# first_model.net
KiCad netlist of a schematic drawn in EAGLE
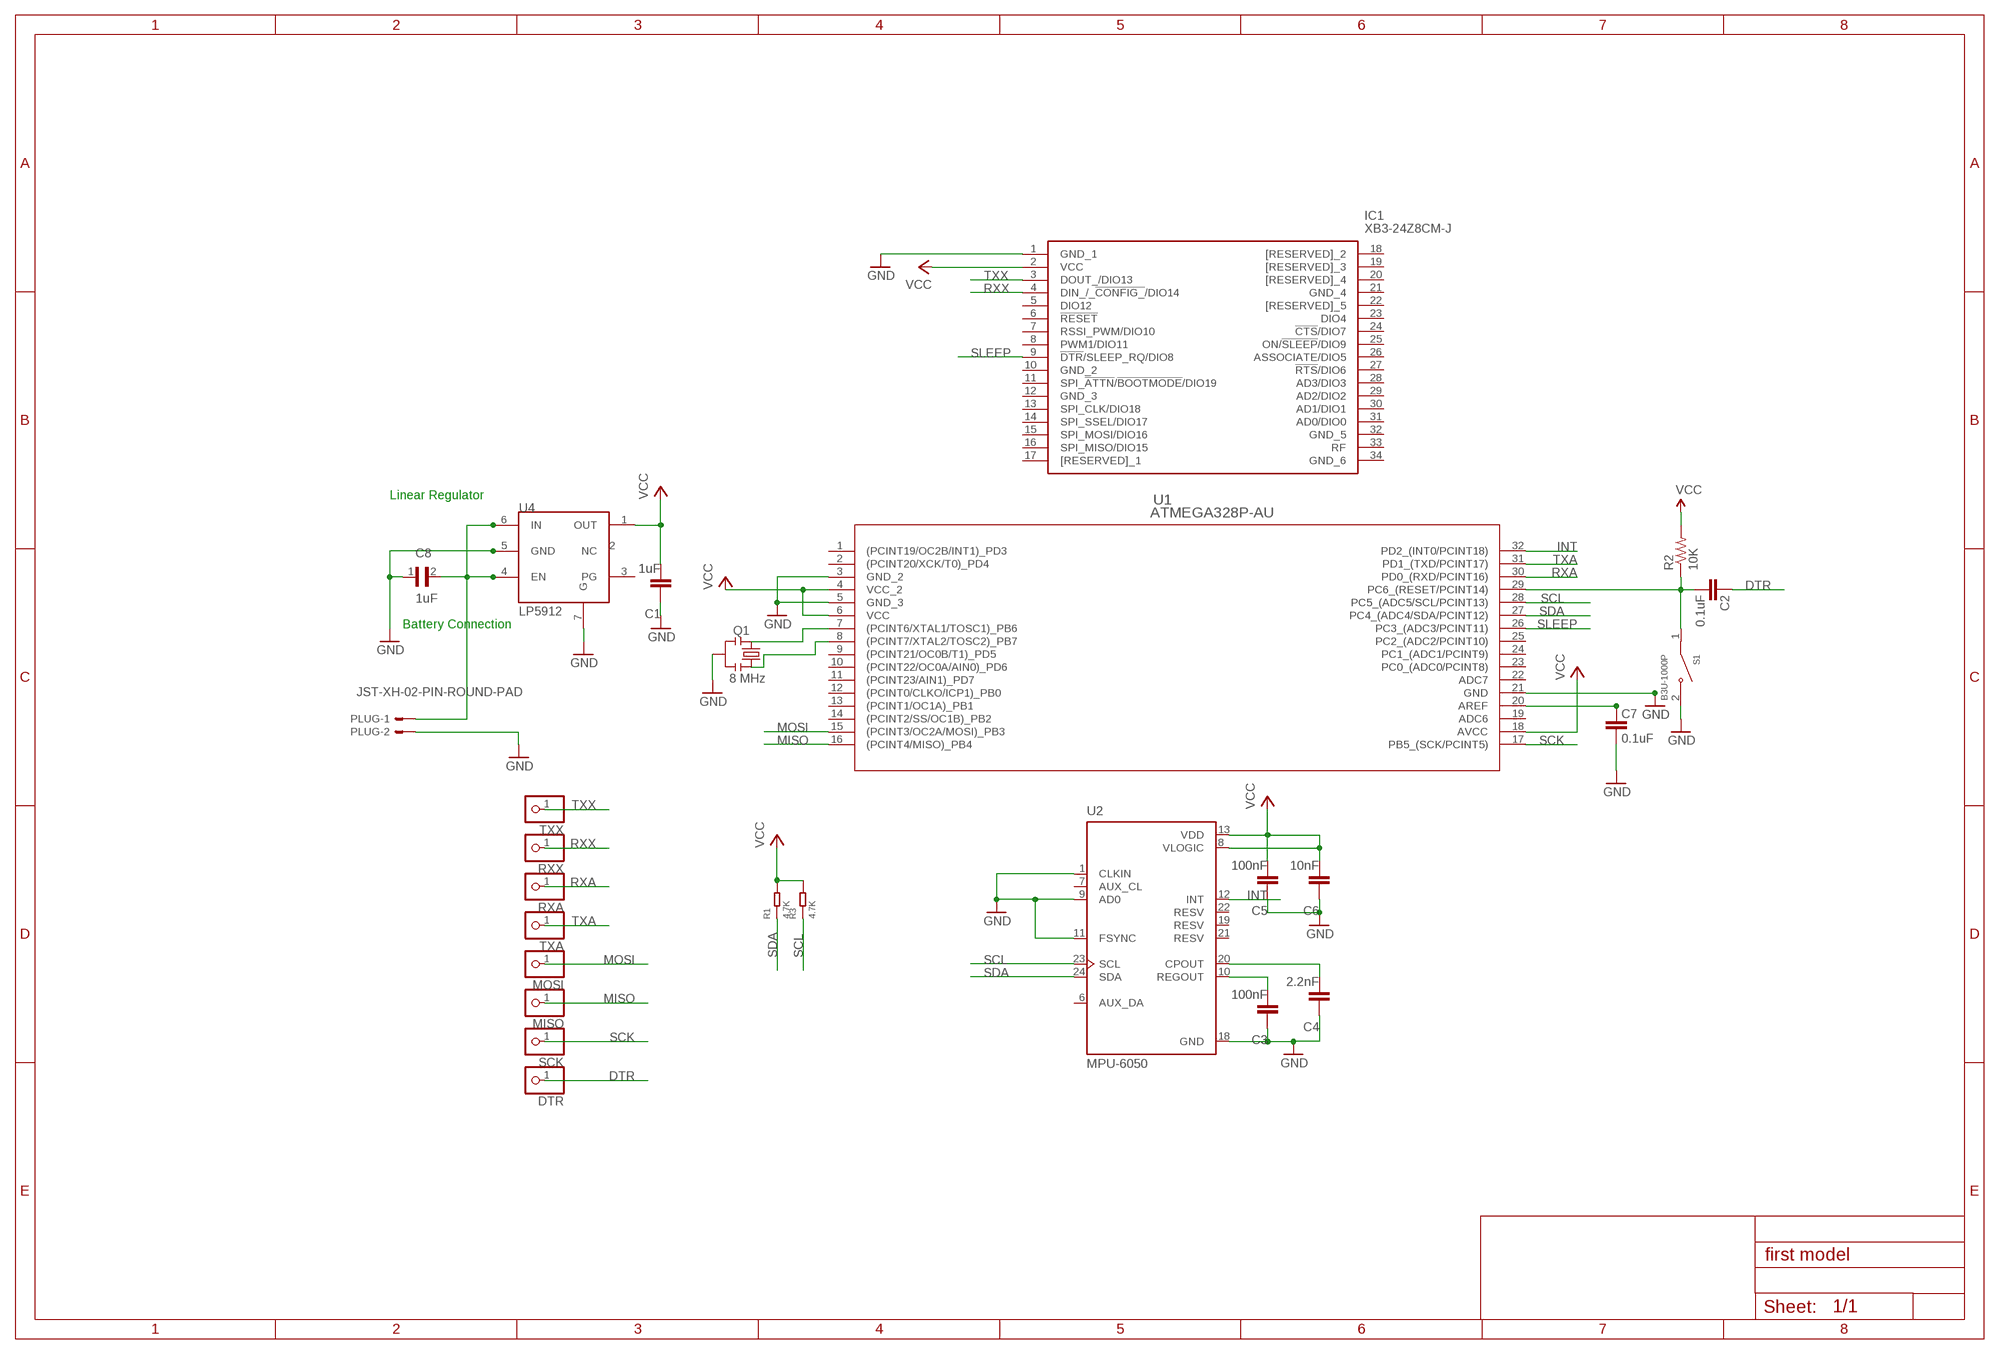
[diagram p0: schematic, sheet 1]

(export (version "E")
  (design (tool "Eeschema 10.0.6"))
  (components
    (comp (ref "C1")
      (value "1uF")
      (footprint "eagle-import:C0603")
      (libsource (lib "eagle-import") (part "C-EUC0603"))
    )
    (comp (ref "C2")
      (value "0.1uF")
      (footprint "eagle-import:0603-CAP")
      (libsource (lib "eagle-import") (part "CAP0603-CAP"))
    )
    (comp (ref "C3")
      (value "100nF")
      (footprint "eagle-import:C0603")
      (libsource (lib "eagle-import") (part "C-EUC0603"))
    )
    (comp (ref "C4")
      (value "2.2nF")
      (footprint "eagle-import:C0603")
      (libsource (lib "eagle-import") (part "C-EUC0603"))
    )
    (comp (ref "C5")
      (value "100nF")
      (footprint "eagle-import:C0603")
      (libsource (lib "eagle-import") (part "C-EUC0603"))
    )
    (comp (ref "C6")
      (value "10nF")
      (footprint "eagle-import:C0603")
      (libsource (lib "eagle-import") (part "C-EUC0603"))
    )
    (comp (ref "C7")
      (value "0.1uF")
      (footprint "eagle-import:0603-CAP")
      (libsource (lib "eagle-import") (part "CAP0603-CAP"))
    )
    (comp (ref "C8")
      (value "1uF")
      (footprint "eagle-import:CAPC1005X71N")
      (fields (field (name "MF") "AVX") (field (name "MP") "0402YD105MAT2A"))
      (libsource (lib "eagle-import") (part "0402YD105MAT2A"))
    )
    (comp (ref "DTR")
      (value "DTR")
      (footprint "eagle-import:1X01")
      (libsource (lib "eagle-import") (part "PINHD-1X1"))
    )
    (comp (ref "IC1")
      (value "XB3-24Z8CM-J")
      (footprint "eagle-import:XB324Z8CMJ")
      (fields (field (name "MOUSER_PART_NUMBER") "888-XB3-24Z8CM-J"))
      (libsource (lib "eagle-import") (part "XB3-24Z8CM-J"))
    )
    (comp (ref "MISO")
      (value "PINHD-1X1")
      (footprint "eagle-import:1X01")
      (libsource (lib "eagle-import") (part "PINHD-1X1"))
    )
    (comp (ref "MOSI")
      (value "PINHD-1X1")
      (footprint "eagle-import:1X01")
      (libsource (lib "eagle-import") (part "PINHD-1X1"))
    )
    (comp (ref "PLUG")
      (value "JST-XH-02-PIN-ROUND-PAD")
      (footprint "eagle-import:JST-XH-02-PACKAGE-ROUND-PAD")
      (libsource (lib "eagle-import") (part "JST-XH-02-PIN-ROUND-PAD"))
    )
    (comp (ref "Q1")
      (value "8 MHz")
      (footprint "eagle-import:RESONATOR-SMD-1_1")
      (libsource (lib "eagle-import") (part "RESONATOR1{colon}1"))
    )
    (comp (ref "R1")
      (value "4.7K")
      (footprint "eagle-import:R0402")
      (fields (field (name "MF") "Yageo") (field (name "MP") "RC0402JR074K7L"))
      (libsource (lib "eagle-import") (part "SMD-RES-4.7K-5%-1/16W(0402)"))
    )
    (comp (ref "R2")
      (value "10K")
      (footprint "eagle-import:0603-RES")
      (libsource (lib "eagle-import") (part "RESISTOR0603-RES"))
    )
    (comp (ref "R3")
      (value "4.7K")
      (footprint "eagle-import:R0402")
      (fields (field (name "MF") "Yageo") (field (name "MP") "RC0402JR074K7L"))
      (libsource (lib "eagle-import") (part "SMD-RES-4.7K-5%-1/16W(0402)"))
    )
    (comp (ref "RXA")
      (value "PINHD-1X1")
      (footprint "eagle-import:1X01")
      (libsource (lib "eagle-import") (part "PINHD-1X1"))
    )
    (comp (ref "RXX")
      (value "PINHD-1X1")
      (footprint "eagle-import:1X01")
      (libsource (lib "eagle-import") (part "PINHD-1X1"))
    )
    (comp (ref "S1")
      (value "B3U-1000P")
      (footprint "eagle-import:SW_B3U-1000P")
      (fields (field (name "MF") "Omron"))
      (libsource (lib "eagle-import") (part "B3U-1000P"))
    )
    (comp (ref "SCK")
      (value "PINHD-1X1")
      (footprint "eagle-import:1X01")
      (fields (field (name "SPICEPREFIX") "X"))
      (libsource (lib "eagle-import") (part "PINHD-1X1"))
    )
    (comp (ref "TXA")
      (value "PINHD-1X1")
      (footprint "eagle-import:1X01")
      (libsource (lib "eagle-import") (part "PINHD-1X1"))
    )
    (comp (ref "TXX")
      (value "PINHD-1X1")
      (footprint "eagle-import:1X01")
      (libsource (lib "eagle-import") (part "PINHD-1X1"))
    )
    (comp (ref "U1")
      (value "ATMEGA328P-AU")
      (footprint "eagle-import:32A")
      (libsource (lib "eagle-import") (part "ATMEGA328P-AU"))
    )
    (comp (ref "U2")
      (value "MPU-6050")
      (footprint "eagle-import:QFN50P400X400X95-24N")
      (fields (field (name "MF") "TDK InvenSense"))
      (libsource (lib "eagle-import") (part "MPU-6050"))
    )
    (comp (ref "U4")
      (value "LP5912")
      (footprint "eagle-import:LP5912")
      (libsource (lib "eagle-import") (part "LP5912"))
    )
  )
  (nets
    (net (code "1") (name "/DTR") (class "Default")
      (node (ref "C2") (pin "2") (pinfunction "2_2") (pintype "passive"))
      (node (ref "DTR") (pin "1") (pinfunction "1_1") (pintype "passive"))
    )
    (net (code "2") (name "/INT") (class "Default")
      (node (ref "U1") (pin "32") (pinfunction "PD2_(INT0/PCINT18)_32") (pintype "bidirectional"))
      (node (ref "U2") (pin "12") (pinfunction "INT_12") (pintype "output"))
    )
    (net (code "3") (name "/MISO") (class "Default")
      (node (ref "MISO") (pin "1") (pinfunction "1_1") (pintype "passive"))
      (node (ref "U1") (pin "16") (pinfunction "(PCINT4/MISO)_PB4_16") (pintype "bidirectional"))
    )
    (net (code "4") (name "/MOSI") (class "Default")
      (node (ref "MOSI") (pin "1") (pinfunction "1_1") (pintype "passive"))
      (node (ref "U1") (pin "15") (pinfunction "(PCINT3/OC2A/MOSI)_PB3_15") (pintype "bidirectional"))
    )
    (net (code "5") (name "/RXA") (class "Default")
      (node (ref "RXA") (pin "1") (pinfunction "1_1") (pintype "passive"))
      (node (ref "U1") (pin "30") (pinfunction "PD0_(RXD/PCINT16)_30") (pintype "bidirectional"))
    )
    (net (code "6") (name "/RXX") (class "Default")
      (node (ref "IC1") (pin "4") (pinfunction "DIN_/_~{CONFIG_}/DIO14_4") (pintype "bidirectional"))
      (node (ref "RXX") (pin "1") (pinfunction "1_1") (pintype "passive"))
    )
    (net (code "7") (name "/SCK") (class "Default")
      (node (ref "SCK") (pin "1") (pinfunction "1_1") (pintype "passive"))
      (node (ref "U1") (pin "17") (pinfunction "PB5_(SCK/PCINT5)_17") (pintype "bidirectional"))
    )
    (net (code "8") (name "/SCL") (class "Default")
      (node (ref "R3") (pin "1") (pinfunction "1_1") (pintype "passive"))
      (node (ref "U1") (pin "28") (pinfunction "PC5_(ADC5/SCL/PCINT13)_28") (pintype "bidirectional"))
      (node (ref "U2") (pin "23") (pinfunction "SCL_23") (pintype "input"))
    )
    (net (code "9") (name "/SDA") (class "Default")
      (node (ref "R1") (pin "1") (pinfunction "1_1") (pintype "passive"))
      (node (ref "U1") (pin "27") (pinfunction "PC4_(ADC4/SDA/PCINT12)_27") (pintype "bidirectional"))
      (node (ref "U2") (pin "24") (pinfunction "SDA_24") (pintype "bidirectional"))
    )
    (net (code "10") (name "/SLEEP") (class "Default")
      (node (ref "IC1") (pin "9") (pinfunction "~{DTR}/SLEEP_RQ/DIO8_9") (pintype "bidirectional"))
      (node (ref "U1") (pin "26") (pinfunction "PC3_(ADC3/PCINT11)_26") (pintype "bidirectional"))
    )
    (net (code "11") (name "/TXA") (class "Default")
      (node (ref "TXA") (pin "1") (pinfunction "1_1") (pintype "passive"))
      (node (ref "U1") (pin "31") (pinfunction "PD1_(TXD/PCINT17)_31") (pintype "bidirectional"))
    )
    (net (code "12") (name "/TXX") (class "Default")
      (node (ref "IC1") (pin "3") (pinfunction "DOUT_/DIO13_3") (pintype "bidirectional"))
      (node (ref "TXX") (pin "1") (pinfunction "1_1") (pintype "passive"))
    )
    (net (code "13") (name "GND") (class "Default")
      (node (ref "C1") (pin "1") (pinfunction "1_1") (pintype "passive"))
      (node (ref "C3") (pin "1") (pinfunction "1_1") (pintype "passive"))
      (node (ref "C4") (pin "1") (pinfunction "1_1") (pintype "passive"))
      (node (ref "C5") (pin "1") (pinfunction "1_1") (pintype "passive"))
      (node (ref "C6") (pin "1") (pinfunction "1_1") (pintype "passive"))
      (node (ref "C7") (pin "1") (pinfunction "1_1") (pintype "passive"))
      (node (ref "C8") (pin "1") (pinfunction "1_1") (pintype "passive"))
      (node (ref "IC1") (pin "1") (pinfunction "GND_1_1") (pintype "bidirectional"))
      (node (ref "PLUG") (pin "2") (pinfunction "S_2") (pintype "passive"))
      (node (ref "Q1") (pin "2") (pinfunction "2_2") (pintype "passive"))
      (node (ref "S1") (pin "2") (pinfunction "2_2") (pintype "passive"))
      (node (ref "U1") (pin "21") (pinfunction "GND_21") (pintype "power_in"))
      (node (ref "U1") (pin "3") (pinfunction "GND_2_3") (pintype "power_in"))
      (node (ref "U1") (pin "5") (pinfunction "GND_3_5") (pintype "power_in"))
      (node (ref "U2") (pin "1") (pinfunction "CLKIN_1") (pintype "input"))
      (node (ref "U2") (pin "11") (pinfunction "FSYNC_11") (pintype "input"))
      (node (ref "U2") (pin "18") (pinfunction "GND_18") (pintype "power_in"))
      (node (ref "U2") (pin "9") (pinfunction "AD0_9") (pintype "input"))
      (node (ref "U4") (pin "5") (pinfunction "GND_5") (pintype "power_in"))
      (node (ref "U4") (pin "7") (pinfunction "G_7") (pintype "bidirectional"))
    )
    (net (code "14") (name "Net-(PLUGA-S)") (class "Default")
      (node (ref "C8") (pin "2") (pinfunction "2_2") (pintype "passive"))
      (node (ref "PLUG") (pin "1") (pinfunction "S_1") (pintype "passive"))
      (node (ref "U4") (pin "4") (pinfunction "EN_4") (pintype "bidirectional"))
      (node (ref "U4") (pin "6") (pinfunction "IN_6") (pintype "power_in"))
    )
    (net (code "15") (name "Net-(U1-(PCINT6{slash}XTAL1{slash}TOSC1)_PB6)") (class "Default")
      (node (ref "Q1") (pin "1") (pinfunction "1_1") (pintype "passive"))
      (node (ref "U1") (pin "7") (pinfunction "(PCINT6/XTAL1/TOSC1)_PB6_7") (pintype "bidirectional"))
    )
    (net (code "16") (name "Net-(U1-(PCINT7{slash}XTAL2{slash}TOSC2)_PB7)") (class "Default")
      (node (ref "Q1") (pin "3") (pinfunction "3_3") (pintype "passive"))
      (node (ref "U1") (pin "8") (pinfunction "(PCINT7/XTAL2/TOSC2)_PB7_8") (pintype "bidirectional"))
    )
    (net (code "17") (name "Net-(U1-AREF)") (class "Default")
      (node (ref "C7") (pin "2") (pinfunction "2_2") (pintype "passive"))
      (node (ref "U1") (pin "20") (pinfunction "AREF_20") (pintype "passive"))
    )
    (net (code "18") (name "Net-(U1-PC6_(RESET{slash}PCINT14))") (class "Default")
      (node (ref "C2") (pin "1") (pinfunction "1_1") (pintype "passive"))
      (node (ref "R2") (pin "1") (pinfunction "1_1") (pintype "passive"))
      (node (ref "S1") (pin "1") (pinfunction "1_1") (pintype "passive"))
      (node (ref "U1") (pin "29") (pinfunction "PC6_(RESET/PCINT14)_29") (pintype "bidirectional"))
    )
    (net (code "19") (name "Net-(U2-CPOUT)") (class "Default")
      (node (ref "C4") (pin "2") (pinfunction "2_2") (pintype "passive"))
      (node (ref "U2") (pin "20") (pinfunction "CPOUT_20") (pintype "passive"))
    )
    (net (code "20") (name "Net-(U2-REGOUT)") (class "Default")
      (node (ref "C3") (pin "2") (pinfunction "2_2") (pintype "passive"))
      (node (ref "U2") (pin "10") (pinfunction "REGOUT_10") (pintype "passive"))
    )
    (net (code "21") (name "VCC") (class "Default")
      (node (ref "C1") (pin "2") (pinfunction "2_2") (pintype "passive"))
      (node (ref "C5") (pin "2") (pinfunction "2_2") (pintype "passive"))
      (node (ref "C6") (pin "2") (pinfunction "2_2") (pintype "passive"))
      (node (ref "IC1") (pin "2") (pinfunction "VCC_2") (pintype "bidirectional"))
      (node (ref "R1") (pin "2") (pinfunction "2_2") (pintype "passive"))
      (node (ref "R2") (pin "2") (pinfunction "2_2") (pintype "passive"))
      (node (ref "R3") (pin "2") (pinfunction "2_2") (pintype "passive"))
      (node (ref "U1") (pin "18") (pinfunction "AVCC_18") (pintype "power_in"))
      (node (ref "U1") (pin "4") (pinfunction "VCC_2_4") (pintype "power_in"))
      (node (ref "U1") (pin "6") (pinfunction "VCC_6") (pintype "power_in"))
      (node (ref "U2") (pin "13") (pinfunction "VDD_13") (pintype "power_in"))
      (node (ref "U2") (pin "8") (pinfunction "VLOGIC_8") (pintype "power_in"))
      (node (ref "U4") (pin "1") (pinfunction "OUT_1") (pintype "power_in"))
    )
    (net (code "22") (name "unconnected-(IC1-AD0{slash}DIO0-Pad31)") (class "Default")
      (node (ref "IC1") (pin "31") (pinfunction "AD0/DIO0_31") (pintype "bidirectional"))
    )
    (net (code "23") (name "unconnected-(IC1-AD1{slash}DIO1-Pad30)") (class "Default")
      (node (ref "IC1") (pin "30") (pinfunction "AD1/DIO1_30") (pintype "bidirectional"))
    )
    (net (code "24") (name "unconnected-(IC1-AD2{slash}DIO2-Pad29)") (class "Default")
      (node (ref "IC1") (pin "29") (pinfunction "AD2/DIO2_29") (pintype "bidirectional"))
    )
    (net (code "25") (name "unconnected-(IC1-AD3{slash}DIO3-Pad28)") (class "Default")
      (node (ref "IC1") (pin "28") (pinfunction "AD3/DIO3_28") (pintype "bidirectional"))
    )
    (net (code "26") (name "unconnected-(IC1-ASSOCIATE{slash}DIO5-Pad26)") (class "Default")
      (node (ref "IC1") (pin "26") (pinfunction "ASSOCIATE/DIO5_26") (pintype "bidirectional"))
    )
    (net (code "27") (name "unconnected-(IC1-DIO4-Pad23)") (class "Default")
      (node (ref "IC1") (pin "23") (pinfunction "DIO4_23") (pintype "bidirectional"))
    )
    (net (code "28") (name "unconnected-(IC1-DIO12-Pad5)") (class "Default")
      (node (ref "IC1") (pin "5") (pinfunction "DIO12_5") (pintype "bidirectional"))
    )
    (net (code "29") (name "unconnected-(IC1-GND_2-Pad10)") (class "Default")
      (node (ref "IC1") (pin "10") (pinfunction "GND_2_10") (pintype "bidirectional"))
    )
    (net (code "30") (name "unconnected-(IC1-GND_3-Pad12)") (class "Default")
      (node (ref "IC1") (pin "12") (pinfunction "GND_3_12") (pintype "bidirectional"))
    )
    (net (code "31") (name "unconnected-(IC1-GND_4-Pad21)") (class "Default")
      (node (ref "IC1") (pin "21") (pinfunction "GND_4_21") (pintype "bidirectional"))
    )
    (net (code "32") (name "unconnected-(IC1-GND_5-Pad32)") (class "Default")
      (node (ref "IC1") (pin "32") (pinfunction "GND_5_32") (pintype "bidirectional"))
    )
    (net (code "33") (name "unconnected-(IC1-GND_6-Pad34)") (class "Default")
      (node (ref "IC1") (pin "34") (pinfunction "GND_6_34") (pintype "bidirectional"))
    )
    (net (code "34") (name "unconnected-(IC1-ON{slash}~{SLEEP}{slash}DIO9-Pad25)") (class "Default")
      (node (ref "IC1") (pin "25") (pinfunction "ON/~{SLEEP}/DIO9_25") (pintype "bidirectional"))
    )
    (net (code "35") (name "unconnected-(IC1-PWM1{slash}DIO11-Pad8)") (class "Default")
      (node (ref "IC1") (pin "8") (pinfunction "PWM1/DIO11_8") (pintype "bidirectional"))
    )
    (net (code "36") (name "unconnected-(IC1-RF-Pad33)") (class "Default")
      (node (ref "IC1") (pin "33") (pinfunction "RF_33") (pintype "bidirectional"))
    )
    (net (code "37") (name "unconnected-(IC1-RSSI_PWM{slash}DIO10-Pad7)") (class "Default")
      (node (ref "IC1") (pin "7") (pinfunction "RSSI_PWM/DIO10_7") (pintype "bidirectional"))
    )
    (net (code "38") (name "unconnected-(IC1-SPI_CLK{slash}DIO18-Pad13)") (class "Default")
      (node (ref "IC1") (pin "13") (pinfunction "SPI_CLK/DIO18_13") (pintype "bidirectional"))
    )
    (net (code "39") (name "unconnected-(IC1-SPI_MISO{slash}DIO15-Pad16)") (class "Default")
      (node (ref "IC1") (pin "16") (pinfunction "SPI_MISO/DIO15_16") (pintype "bidirectional"))
    )
    (net (code "40") (name "unconnected-(IC1-SPI_MOSI{slash}DIO16-Pad15)") (class "Default")
      (node (ref "IC1") (pin "15") (pinfunction "SPI_MOSI/DIO16_15") (pintype "bidirectional"))
    )
    (net (code "41") (name "unconnected-(IC1-SPI_SSEL{slash}DIO17-Pad14)") (class "Default")
      (node (ref "IC1") (pin "14") (pinfunction "SPI_SSEL/DIO17_14") (pintype "bidirectional"))
    )
    (net (code "42") (name "unconnected-(IC1-SPI_~{ATTN}{slash}~{BOOTMODE}{slash}DIO19-Pad11)") (class "Default")
      (node (ref "IC1") (pin "11") (pinfunction "SPI_~{ATTN}/~{BOOTMODE}/DIO19_11") (pintype "bidirectional"))
    )
    (net (code "43") (name "unconnected-(IC1-[RESERVED]_1-Pad17)") (class "Default")
      (node (ref "IC1") (pin "17") (pinfunction "[RESERVED]_1_17") (pintype "bidirectional"))
    )
    (net (code "44") (name "unconnected-(IC1-[RESERVED]_2-Pad18)") (class "Default")
      (node (ref "IC1") (pin "18") (pinfunction "[RESERVED]_2_18") (pintype "bidirectional"))
    )
    (net (code "45") (name "unconnected-(IC1-[RESERVED]_3-Pad19)") (class "Default")
      (node (ref "IC1") (pin "19") (pinfunction "[RESERVED]_3_19") (pintype "bidirectional"))
    )
    (net (code "46") (name "unconnected-(IC1-[RESERVED]_4-Pad20)") (class "Default")
      (node (ref "IC1") (pin "20") (pinfunction "[RESERVED]_4_20") (pintype "bidirectional"))
    )
    (net (code "47") (name "unconnected-(IC1-[RESERVED]_5-Pad22)") (class "Default")
      (node (ref "IC1") (pin "22") (pinfunction "[RESERVED]_5_22") (pintype "bidirectional"))
    )
    (net (code "48") (name "unconnected-(IC1-~{CTS}{slash}DIO7-Pad24)") (class "Default")
      (node (ref "IC1") (pin "24") (pinfunction "~{CTS}/DIO7_24") (pintype "bidirectional"))
    )
    (net (code "49") (name "unconnected-(IC1-~{RESET}-Pad6)") (class "Default")
      (node (ref "IC1") (pin "6") (pinfunction "~{RESET}_6") (pintype "bidirectional"))
    )
    (net (code "50") (name "unconnected-(IC1-~{RTS}{slash}DIO6-Pad27)") (class "Default")
      (node (ref "IC1") (pin "27") (pinfunction "~{RTS}/DIO6_27") (pintype "bidirectional"))
    )
    (net (code "51") (name "unconnected-(U1-(PCINT0{slash}CLKO{slash}ICP1)_PB0-Pad12)") (class "Default")
      (node (ref "U1") (pin "12") (pinfunction "(PCINT0/CLKO/ICP1)_PB0_12") (pintype "bidirectional"))
    )
    (net (code "52") (name "unconnected-(U1-(PCINT1{slash}OC1A)_PB1-Pad13)") (class "Default")
      (node (ref "U1") (pin "13") (pinfunction "(PCINT1/OC1A)_PB1_13") (pintype "bidirectional"))
    )
    (net (code "53") (name "unconnected-(U1-(PCINT2{slash}SS{slash}OC1B)_PB2-Pad14)") (class "Default")
      (node (ref "U1") (pin "14") (pinfunction "(PCINT2/SS/OC1B)_PB2_14") (pintype "bidirectional"))
    )
    (net (code "54") (name "unconnected-(U1-(PCINT19{slash}OC2B{slash}INT1)_PD3-Pad1)") (class "Default")
      (node (ref "U1") (pin "1") (pinfunction "(PCINT19/OC2B/INT1)_PD3_1") (pintype "bidirectional"))
    )
    (net (code "55") (name "unconnected-(U1-(PCINT20{slash}XCK{slash}T0)_PD4-Pad2)") (class "Default")
      (node (ref "U1") (pin "2") (pinfunction "(PCINT20/XCK/T0)_PD4_2") (pintype "bidirectional"))
    )
    (net (code "56") (name "unconnected-(U1-(PCINT21{slash}OC0B{slash}T1)_PD5-Pad9)") (class "Default")
      (node (ref "U1") (pin "9") (pinfunction "(PCINT21/OC0B/T1)_PD5_9") (pintype "bidirectional"))
    )
    (net (code "57") (name "unconnected-(U1-(PCINT22{slash}OC0A{slash}AIN0)_PD6-Pad10)") (class "Default")
      (node (ref "U1") (pin "10") (pinfunction "(PCINT22/OC0A/AIN0)_PD6_10") (pintype "bidirectional"))
    )
    (net (code "58") (name "unconnected-(U1-(PCINT23{slash}AIN1)_PD7-Pad11)") (class "Default")
      (node (ref "U1") (pin "11") (pinfunction "(PCINT23/AIN1)_PD7_11") (pintype "bidirectional"))
    )
    (net (code "59") (name "unconnected-(U1-ADC6-Pad19)") (class "Default")
      (node (ref "U1") (pin "19") (pinfunction "ADC6_19") (pintype "input"))
    )
    (net (code "60") (name "unconnected-(U1-ADC7-Pad22)") (class "Default")
      (node (ref "U1") (pin "22") (pinfunction "ADC7_22") (pintype "input"))
    )
    (net (code "61") (name "unconnected-(U1-PC0_(ADC0{slash}PCINT8)-Pad23)") (class "Default")
      (node (ref "U1") (pin "23") (pinfunction "PC0_(ADC0/PCINT8)_23") (pintype "bidirectional"))
    )
    (net (code "62") (name "unconnected-(U1-PC1_(ADC1{slash}PCINT9)-Pad24)") (class "Default")
      (node (ref "U1") (pin "24") (pinfunction "PC1_(ADC1/PCINT9)_24") (pintype "bidirectional"))
    )
    (net (code "63") (name "unconnected-(U1-PC2_(ADC2{slash}PCINT10)-Pad25)") (class "Default")
      (node (ref "U1") (pin "25") (pinfunction "PC2_(ADC2/PCINT10)_25") (pintype "bidirectional"))
    )
    (net (code "64") (name "unconnected-(U2-AUX_CL-Pad7)") (class "Default")
      (node (ref "U2") (pin "7") (pinfunction "AUX_CL_7") (pintype "input"))
    )
    (net (code "65") (name "unconnected-(U2-AUX_DA-Pad6)") (class "Default")
      (node (ref "U2") (pin "6") (pinfunction "AUX_DA_6") (pintype "bidirectional"))
    )
    (net (code "66") (name "unconnected-(U2-RESV-Pad19)") (class "Default")
      (node (ref "U2") (pin "19") (pinfunction "RESV_19") (pintype "passive"))
    )
    (net (code "67") (name "unconnected-(U2-RESV-Pad21)") (class "Default")
      (node (ref "U2") (pin "21") (pinfunction "RESV_21") (pintype "passive"))
    )
    (net (code "68") (name "unconnected-(U2-RESV-Pad22)") (class "Default")
      (node (ref "U2") (pin "22") (pinfunction "RESV_22") (pintype "passive"))
    )
    (net (code "69") (name "unconnected-(U4-NC-Pad2)") (class "Default")
      (node (ref "U4") (pin "2") (pinfunction "NC_2") (pintype "bidirectional"))
    )
    (net (code "70") (name "unconnected-(U4-PG-Pad3)") (class "Default")
      (node (ref "U4") (pin "3") (pinfunction "PG_3") (pintype "bidirectional"))
    )
  )
)
